# Imprimir.net
KiCad netlist of a schematic drawn in EAGLE
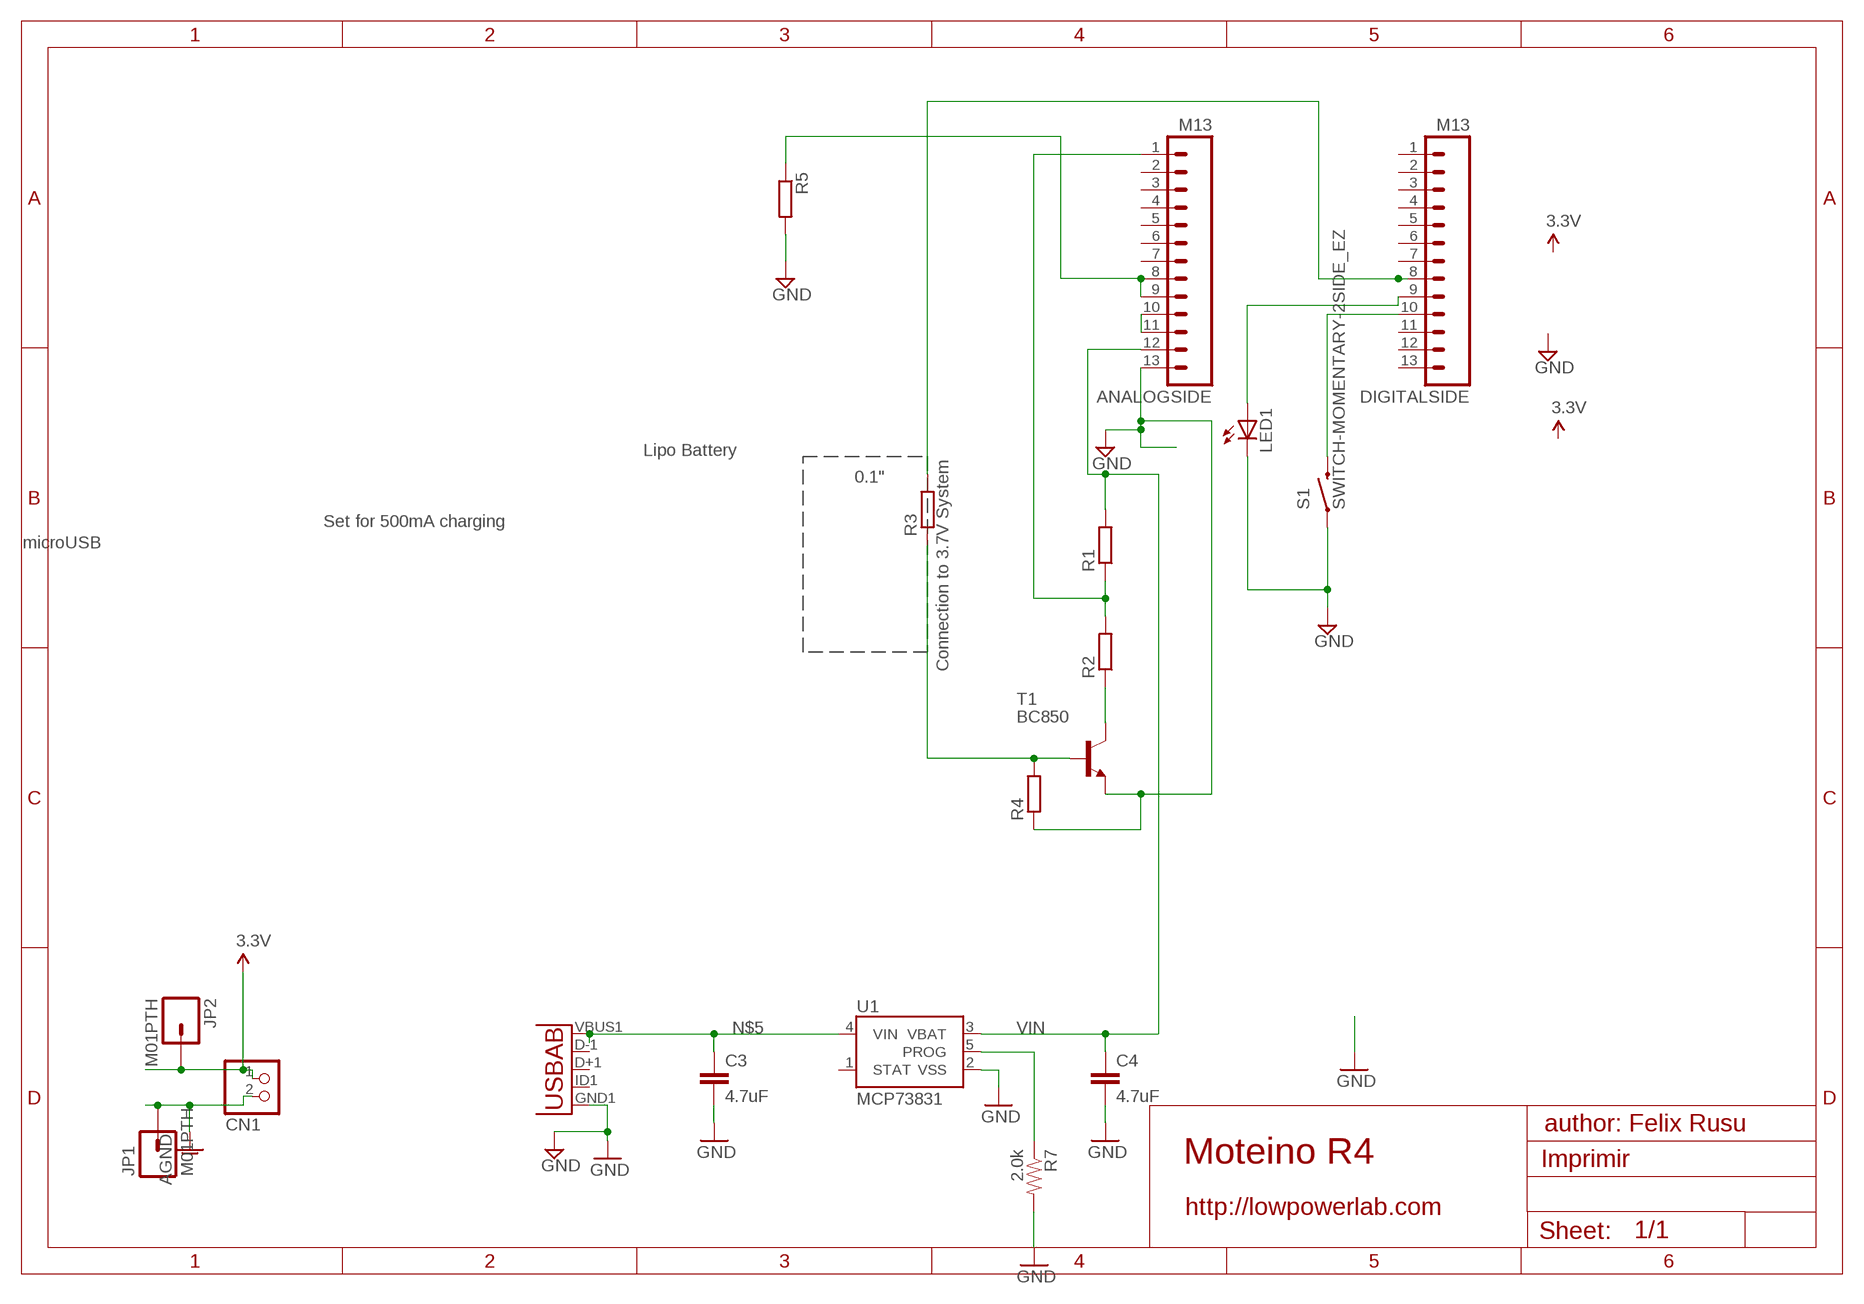
[diagram p0: schematic, sheet 1]

(export (version "E")
  (design (tool "Eeschema 10.0.6"))
  (components
    (comp (ref "ANALOGSIDE")
      (value "M13")
      (footprint "eagle-import:1X13")
      (libsource (lib "eagle-import") (part "M13"))
    )
    (comp (ref "C3")
      (value "4.7uF")
      (footprint "eagle-import:0603-CAP")
      (libsource (lib "eagle-import") (part "4.7UF-6.3V-10%(0603)0603"))
    )
    (comp (ref "C4")
      (value "4.7uF")
      (footprint "eagle-import:0603-CAP")
      (libsource (lib "eagle-import") (part "4.7UF-6.3V-10%(0603)0603"))
    )
    (comp (ref "CN1")
      (value "JST_2PIN-SMT")
      (footprint "eagle-import:JST-PH-2-SMT")
      (libsource (lib "eagle-import") (part "JST_2PIN-SMT"))
    )
    (comp (ref "DIGITALSIDE")
      (value "M13")
      (footprint "eagle-import:1X13")
      (libsource (lib "eagle-import") (part "M13"))
    )
    (comp (ref "JP1")
      (value "M01PTH")
      (footprint "eagle-import:1X01")
      (libsource (lib "eagle-import") (part "M01PTH"))
    )
    (comp (ref "JP2")
      (value "M01PTH")
      (footprint "eagle-import:1X01")
      (libsource (lib "eagle-import") (part "M01PTH"))
    )
    (comp (ref "JP9")
      (value "Micro USB")
      (footprint "eagle-import:USB-AB-MICRO-SMD_V03")
      (libsource (lib "eagle-import") (part "USB-ABCONN-11794"))
    )
    (comp (ref "LED1")
      (value "LED3MM")
      (footprint "eagle-import:LED3MM")
      (libsource (lib "eagle-import") (part "LED3MM"))
    )
    (comp (ref "R1")
      (value "R-EU_0204/7")
      (footprint "eagle-import:0204_7")
      (libsource (lib "eagle-import") (part "R-EU_0204/7"))
    )
    (comp (ref "R2")
      (value "R-EU_0204/7")
      (footprint "eagle-import:0204_7")
      (libsource (lib "eagle-import") (part "R-EU_0204/7"))
    )
    (comp (ref "R3")
      (value "R-EU_M1206")
      (footprint "eagle-import:M1206")
      (libsource (lib "eagle-import") (part "R-EU_M1206"))
    )
    (comp (ref "R4")
      (value "R-EU_M1206")
      (footprint "eagle-import:M1206")
      (libsource (lib "eagle-import") (part "R-EU_M1206"))
    )
    (comp (ref "R5")
      (value "R-EU_0204/7")
      (footprint "eagle-import:0204_7")
      (libsource (lib "eagle-import") (part "R-EU_0204/7"))
    )
    (comp (ref "R7")
      (value "2.0k")
      (footprint "eagle-import:0603-RES")
      (libsource (lib "eagle-import") (part "2.0KOHM1/10W5%(0603)"))
    )
    (comp (ref "S1")
      (value "SWITCH-MOMENTARY-2SIDE_EZ")
      (footprint "eagle-import:TACTILE-PTH-SIDEEZ")
      (libsource (lib "eagle-import") (part "SWITCH-MOMENTARY-2SIDE_EZ"))
    )
    (comp (ref "T1")
      (value "BC850")
      (footprint "eagle-import:SOT23")
      (libsource (lib "eagle-import") (part "BC850"))
    )
    (comp (ref "U1")
      (value "MCP73831")
      (footprint "eagle-import:SOT23-5")
      (libsource (lib "eagle-import") (part "MCP73831"))
    )
  )
  (nets
    (net (code "1") (name "/N$5") (class "Default")
      (node (ref "C3") (pin "1") (pinfunction "1_1") (pintype "passive"))
      (node (ref "JP9") (pin "VBUS1") (pinfunction "VBUS_VBUS1") (pintype "bidirectional"))
      (node (ref "U1") (pin "4") (pinfunction "VIN_4") (pintype "power_in"))
    )
    (net (code "2") (name "/VIN") (class "Default")
      (node (ref "ANALOGSIDE") (pin "12") (pinfunction "12_12") (pintype "passive"))
      (node (ref "C4") (pin "1") (pinfunction "1_1") (pintype "passive"))
      (node (ref "R1") (pin "2") (pinfunction "2_2") (pintype "passive"))
      (node (ref "U1") (pin "3") (pinfunction "VBAT_3") (pintype "power_in"))
    )
    (net (code "3") (name "3.3V") (class "Default")
      (node (ref "CN1") (pin "1") (pinfunction "2_1") (pintype "passive"))
      (node (ref "JP2") (pin "1") (pinfunction "1_1") (pintype "passive"))
    )
    (net (code "4") (name "AGND") (class "Default")
      (node (ref "CN1") (pin "2") (pinfunction "1_2") (pintype "passive"))
      (node (ref "JP1") (pin "1") (pinfunction "1_1") (pintype "passive"))
    )
    (net (code "5") (name "GND") (class "Default")
      (node (ref "ANALOGSIDE") (pin "13") (pinfunction "13_13") (pintype "passive"))
      (node (ref "C3") (pin "2") (pinfunction "2_2") (pintype "passive"))
      (node (ref "C4") (pin "2") (pinfunction "2_2") (pintype "passive"))
      (node (ref "JP9") (pin "GND1") (pinfunction "GND_GND1") (pintype "bidirectional"))
      (node (ref "LED1") (pin "K") (pinfunction "C_K") (pintype "passive"))
      (node (ref "R4") (pin "1") (pinfunction "1_1") (pintype "passive"))
      (node (ref "R5") (pin "2") (pinfunction "2_2") (pintype "passive"))
      (node (ref "R7") (pin "2") (pinfunction "2_2") (pintype "passive"))
      (node (ref "S1") (pin "1") (pinfunction "1_1") (pintype "passive"))
      (node (ref "T1") (pin "2") (pinfunction "E_2") (pintype "passive"))
      (node (ref "U1") (pin "2") (pinfunction "VSS_2") (pintype "power_in"))
    )
    (net (code "6") (name "Net-(ANALOGSIDE-Pad1)") (class "Default")
      (node (ref "ANALOGSIDE") (pin "1") (pinfunction "1_1") (pintype "passive"))
      (node (ref "R1") (pin "1") (pinfunction "1_1") (pintype "passive"))
      (node (ref "R2") (pin "2") (pinfunction "2_2") (pintype "passive"))
    )
    (net (code "7") (name "Net-(ANALOGSIDE-Pad8)") (class "Default")
      (node (ref "ANALOGSIDE") (pin "8") (pinfunction "8_8") (pintype "passive"))
      (node (ref "ANALOGSIDE") (pin "9") (pinfunction "9_9") (pintype "passive"))
      (node (ref "R5") (pin "1") (pinfunction "1_1") (pintype "passive"))
    )
    (net (code "8") (name "Net-(ANALOGSIDE-Pad10)") (class "Default")
      (node (ref "ANALOGSIDE") (pin "10") (pinfunction "10_10") (pintype "passive"))
      (node (ref "ANALOGSIDE") (pin "11") (pinfunction "11_11") (pintype "passive"))
    )
    (net (code "9") (name "Net-(DIGITALSIDE-Pad8)") (class "Default")
      (node (ref "DIGITALSIDE") (pin "8") (pinfunction "8_8") (pintype "passive"))
      (node (ref "R3") (pin "2") (pinfunction "2_2") (pintype "passive"))
    )
    (net (code "10") (name "Net-(DIGITALSIDE-Pad9)") (class "Default")
      (node (ref "DIGITALSIDE") (pin "9") (pinfunction "9_9") (pintype "passive"))
      (node (ref "LED1") (pin "A") (pinfunction "A_A") (pintype "passive"))
    )
    (net (code "11") (name "Net-(DIGITALSIDE-Pad10)") (class "Default")
      (node (ref "DIGITALSIDE") (pin "10") (pinfunction "10_10") (pintype "passive"))
      (node (ref "S1") (pin "2") (pinfunction "2_2") (pintype "passive"))
    )
    (net (code "12") (name "Net-(T1-B)") (class "Default")
      (node (ref "R3") (pin "1") (pinfunction "1_1") (pintype "passive"))
      (node (ref "R4") (pin "2") (pinfunction "2_2") (pintype "passive"))
      (node (ref "T1") (pin "1") (pinfunction "B_1") (pintype "passive"))
    )
    (net (code "13") (name "Net-(T1-C)") (class "Default")
      (node (ref "R2") (pin "1") (pinfunction "1_1") (pintype "passive"))
      (node (ref "T1") (pin "3") (pinfunction "C_3") (pintype "passive"))
    )
    (net (code "14") (name "Net-(U1-PROG)") (class "Default")
      (node (ref "R7") (pin "1") (pinfunction "1_1") (pintype "passive"))
      (node (ref "U1") (pin "5") (pinfunction "PROG_5") (pintype "input"))
    )
    (net (code "15") (name "unconnected-(ANALOGSIDE-Pad2)") (class "Default")
      (node (ref "ANALOGSIDE") (pin "2") (pinfunction "2_2") (pintype "passive"))
    )
    (net (code "16") (name "unconnected-(ANALOGSIDE-Pad3)") (class "Default")
      (node (ref "ANALOGSIDE") (pin "3") (pinfunction "3_3") (pintype "passive"))
    )
    (net (code "17") (name "unconnected-(ANALOGSIDE-Pad4)") (class "Default")
      (node (ref "ANALOGSIDE") (pin "4") (pinfunction "4_4") (pintype "passive"))
    )
    (net (code "18") (name "unconnected-(ANALOGSIDE-Pad5)") (class "Default")
      (node (ref "ANALOGSIDE") (pin "5") (pinfunction "5_5") (pintype "passive"))
    )
    (net (code "19") (name "unconnected-(ANALOGSIDE-Pad6)") (class "Default")
      (node (ref "ANALOGSIDE") (pin "6") (pinfunction "6_6") (pintype "passive"))
    )
    (net (code "20") (name "unconnected-(ANALOGSIDE-Pad7)") (class "Default")
      (node (ref "ANALOGSIDE") (pin "7") (pinfunction "7_7") (pintype "passive"))
    )
    (net (code "21") (name "unconnected-(DIGITALSIDE-Pad1)") (class "Default")
      (node (ref "DIGITALSIDE") (pin "1") (pinfunction "1_1") (pintype "passive"))
    )
    (net (code "22") (name "unconnected-(DIGITALSIDE-Pad2)") (class "Default")
      (node (ref "DIGITALSIDE") (pin "2") (pinfunction "2_2") (pintype "passive"))
    )
    (net (code "23") (name "unconnected-(DIGITALSIDE-Pad3)") (class "Default")
      (node (ref "DIGITALSIDE") (pin "3") (pinfunction "3_3") (pintype "passive"))
    )
    (net (code "24") (name "unconnected-(DIGITALSIDE-Pad4)") (class "Default")
      (node (ref "DIGITALSIDE") (pin "4") (pinfunction "4_4") (pintype "passive"))
    )
    (net (code "25") (name "unconnected-(DIGITALSIDE-Pad5)") (class "Default")
      (node (ref "DIGITALSIDE") (pin "5") (pinfunction "5_5") (pintype "passive"))
    )
    (net (code "26") (name "unconnected-(DIGITALSIDE-Pad6)") (class "Default")
      (node (ref "DIGITALSIDE") (pin "6") (pinfunction "6_6") (pintype "passive"))
    )
    (net (code "27") (name "unconnected-(DIGITALSIDE-Pad7)") (class "Default")
      (node (ref "DIGITALSIDE") (pin "7") (pinfunction "7_7") (pintype "passive"))
    )
    (net (code "28") (name "unconnected-(DIGITALSIDE-Pad11)") (class "Default")
      (node (ref "DIGITALSIDE") (pin "11") (pinfunction "11_11") (pintype "passive"))
    )
    (net (code "29") (name "unconnected-(DIGITALSIDE-Pad12)") (class "Default")
      (node (ref "DIGITALSIDE") (pin "12") (pinfunction "12_12") (pintype "passive"))
    )
    (net (code "30") (name "unconnected-(DIGITALSIDE-Pad13)") (class "Default")
      (node (ref "DIGITALSIDE") (pin "13") (pinfunction "13_13") (pintype "passive"))
    )
    (net (code "31") (name "unconnected-(JP9-D+-PadD+1)") (class "Default")
      (node (ref "JP9") (pin "D+1") (pinfunction "D+_D+1") (pintype "bidirectional"))
    )
    (net (code "32") (name "unconnected-(JP9-D--PadD-1)") (class "Default")
      (node (ref "JP9") (pin "D-1") (pinfunction "D-_D-1") (pintype "bidirectional"))
    )
    (net (code "33") (name "unconnected-(JP9-USBID-PadID1)") (class "Default")
      (node (ref "JP9") (pin "ID1") (pinfunction "USBID_ID1") (pintype "bidirectional"))
    )
    (net (code "34") (name "unconnected-(U1-STAT-Pad1)") (class "Default")
      (node (ref "U1") (pin "1") (pinfunction "STAT_1") (pintype "output"))
    )
  )
)
